# untitled.net
KiCad netlist of a schematic drawn in EAGLE
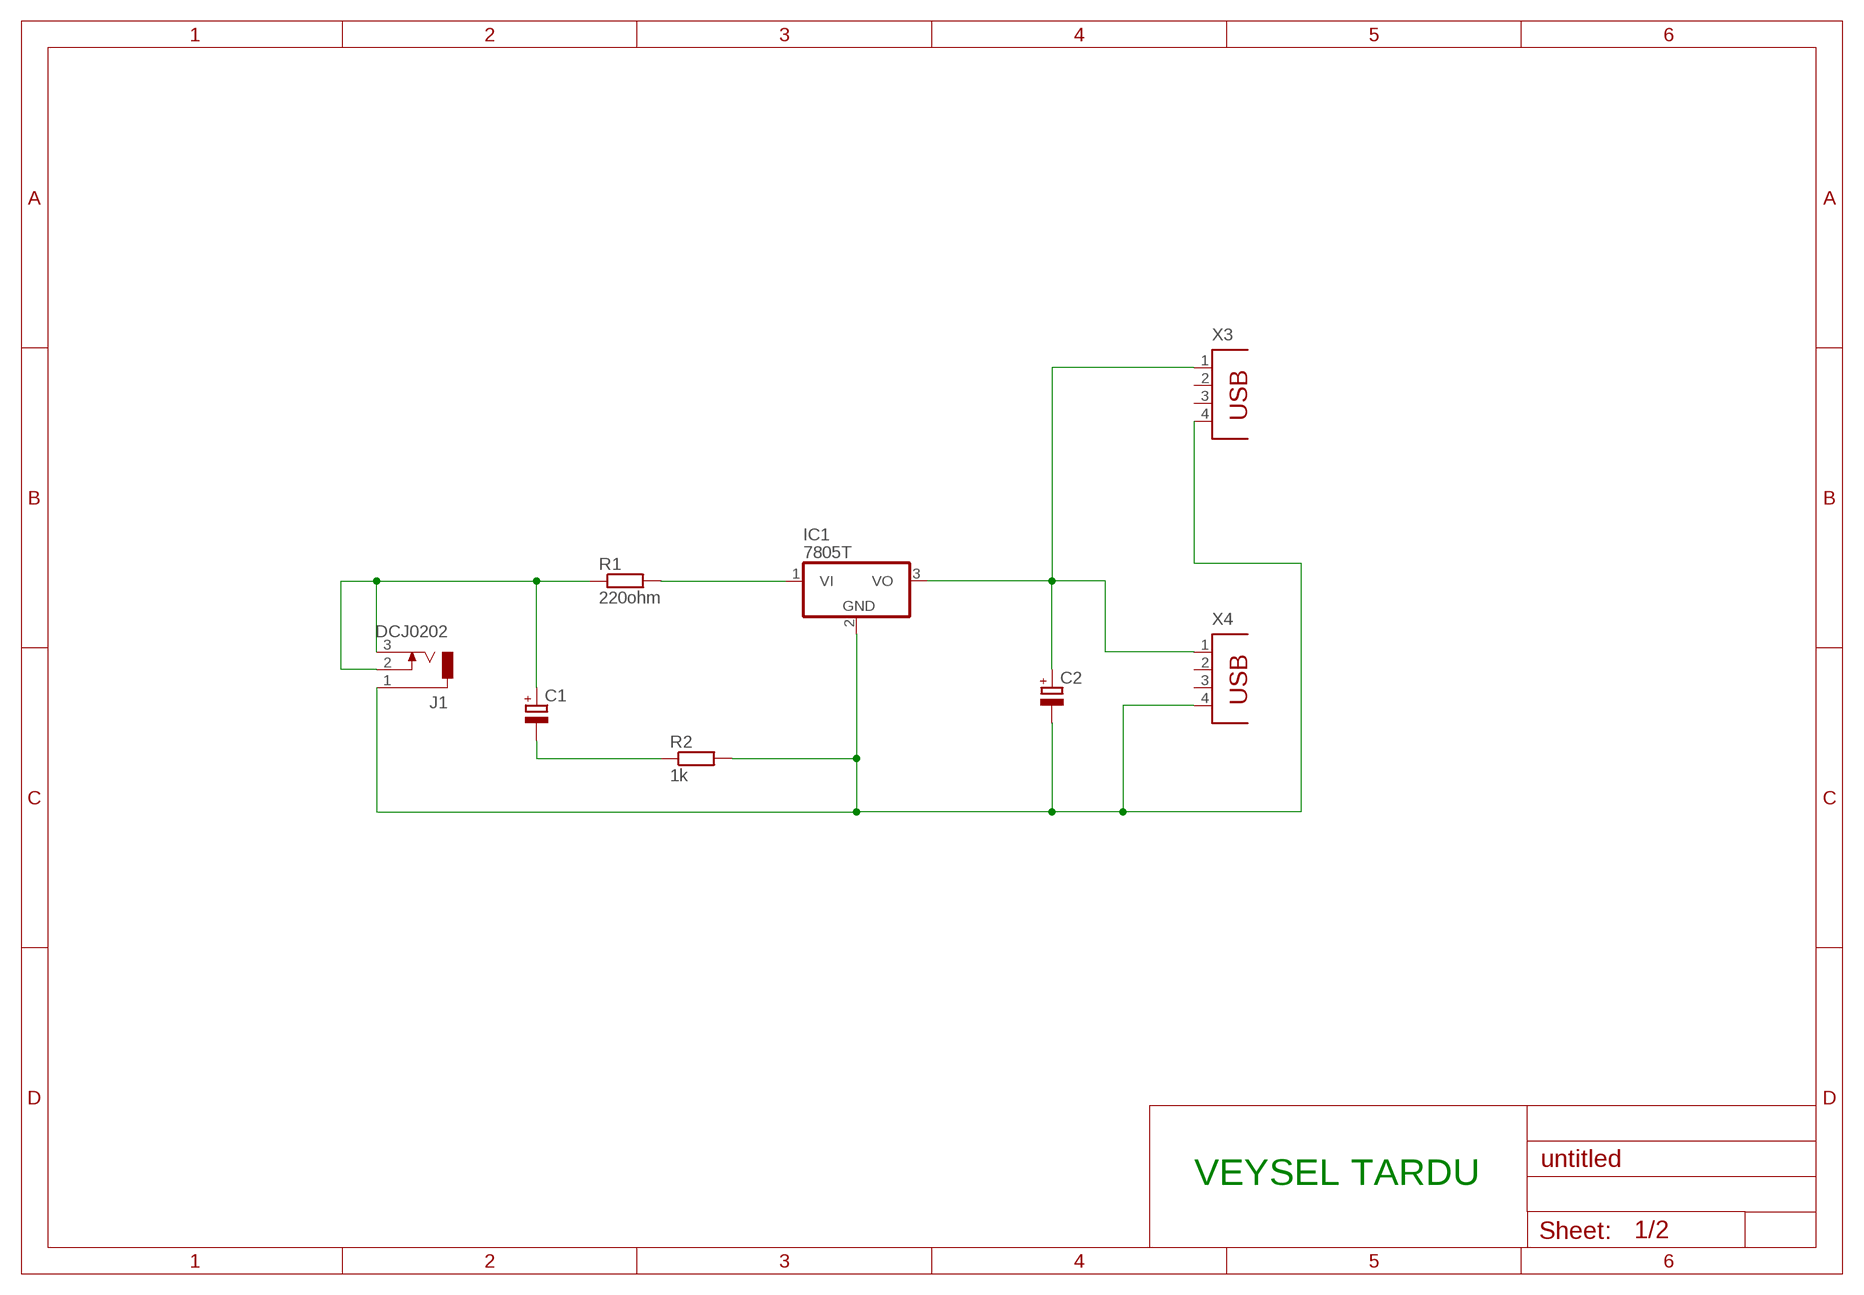
[diagram p0: schematic, sheet 1]

(export (version "E")
  (design (tool "Eeschema 10.0.6"))
  (components
    (comp (ref "C1")
      (value "CPOL-EUE2-5")
      (footprint "eagle-import:E2-5")
      (libsource (lib "eagle-import") (part "CPOL-EUE2-5"))
    )
    (comp (ref "C2")
      (value "CPOL-EUE2-5")
      (footprint "eagle-import:E2-5")
      (libsource (lib "eagle-import") (part "CPOL-EUE2-5"))
    )
    (comp (ref "IC1")
      (value "7805T")
      (footprint "eagle-import:TO220H")
      (libsource (lib "eagle-import") (part "78T05"))
    )
    (comp (ref "J1")
      (value "DCJ0202")
      (footprint "eagle-import:DCJ0202")
      (libsource (lib "eagle-import") (part "DCJ0202"))
    )
    (comp (ref "R1")
      (value "220ohm")
      (footprint "eagle-import:VMTA55")
      (libsource (lib "eagle-import") (part "R-EU_VMTA55"))
    )
    (comp (ref "R2")
      (value "1k")
      (footprint "eagle-import:VMTA55")
      (libsource (lib "eagle-import") (part "R-EU_VMTA55"))
    )
    (comp (ref "X3")
      (value "PN61729")
      (footprint "eagle-import:PN61729")
      (libsource (lib "eagle-import") (part "PN61729"))
    )
    (comp (ref "X4")
      (value "PN61729")
      (footprint "eagle-import:PN61729")
      (libsource (lib "eagle-import") (part "PN61729"))
    )
  )
  (nets
    (net (code "1") (name "Net-(C1-Pad+)") (class "Default")
      (node (ref "C1") (pin "+") (pinfunction "+_+") (pintype "passive"))
      (node (ref "J1") (pin "2") (pinfunction "2_2") (pintype "passive"))
      (node (ref "J1") (pin "3") (pinfunction "3_3") (pintype "passive"))
      (node (ref "R1") (pin "1") (pinfunction "1_1") (pintype "passive"))
    )
    (net (code "2") (name "Net-(C1-Pad-)") (class "Default")
      (node (ref "C1") (pin "-") (pinfunction "-_-") (pintype "passive"))
      (node (ref "R2") (pin "1") (pinfunction "1_1") (pintype "passive"))
    )
    (net (code "3") (name "Net-(IC1-GND)") (class "Default")
      (node (ref "C2") (pin "-") (pinfunction "-_-") (pintype "passive"))
      (node (ref "IC1") (pin "2") (pinfunction "GND_2") (pintype "passive"))
      (node (ref "J1") (pin "1") (pinfunction "1_1") (pintype "passive"))
      (node (ref "R2") (pin "2") (pinfunction "2_2") (pintype "passive"))
      (node (ref "X3") (pin "4") (pinfunction "4_4") (pintype "passive"))
      (node (ref "X4") (pin "4") (pinfunction "4_4") (pintype "passive"))
    )
    (net (code "4") (name "Net-(IC1-VI)") (class "Default")
      (node (ref "IC1") (pin "1") (pinfunction "VI_1") (pintype "input"))
      (node (ref "R1") (pin "2") (pinfunction "2_2") (pintype "passive"))
    )
    (net (code "5") (name "Net-(IC1-VO)") (class "Default")
      (node (ref "C2") (pin "+") (pinfunction "+_+") (pintype "passive"))
      (node (ref "IC1") (pin "3") (pinfunction "VO_3") (pintype "passive"))
      (node (ref "X3") (pin "1") (pinfunction "1_1") (pintype "passive"))
      (node (ref "X4") (pin "1") (pinfunction "1_1") (pintype "passive"))
    )
    (net (code "6") (name "unconnected-(X3-Pad2)") (class "Default")
      (node (ref "X3") (pin "2") (pinfunction "2_2") (pintype "passive"))
    )
    (net (code "7") (name "unconnected-(X3-Pad3)") (class "Default")
      (node (ref "X3") (pin "3") (pinfunction "3_3") (pintype "passive"))
    )
    (net (code "8") (name "unconnected-(X4-Pad2)") (class "Default")
      (node (ref "X4") (pin "2") (pinfunction "2_2") (pintype "passive"))
    )
    (net (code "9") (name "unconnected-(X4-Pad3)") (class "Default")
      (node (ref "X4") (pin "3") (pinfunction "3_3") (pintype "passive"))
    )
  )
)
